# board_0_6v.net
KiCad netlist of a schematic drawn in EAGLE
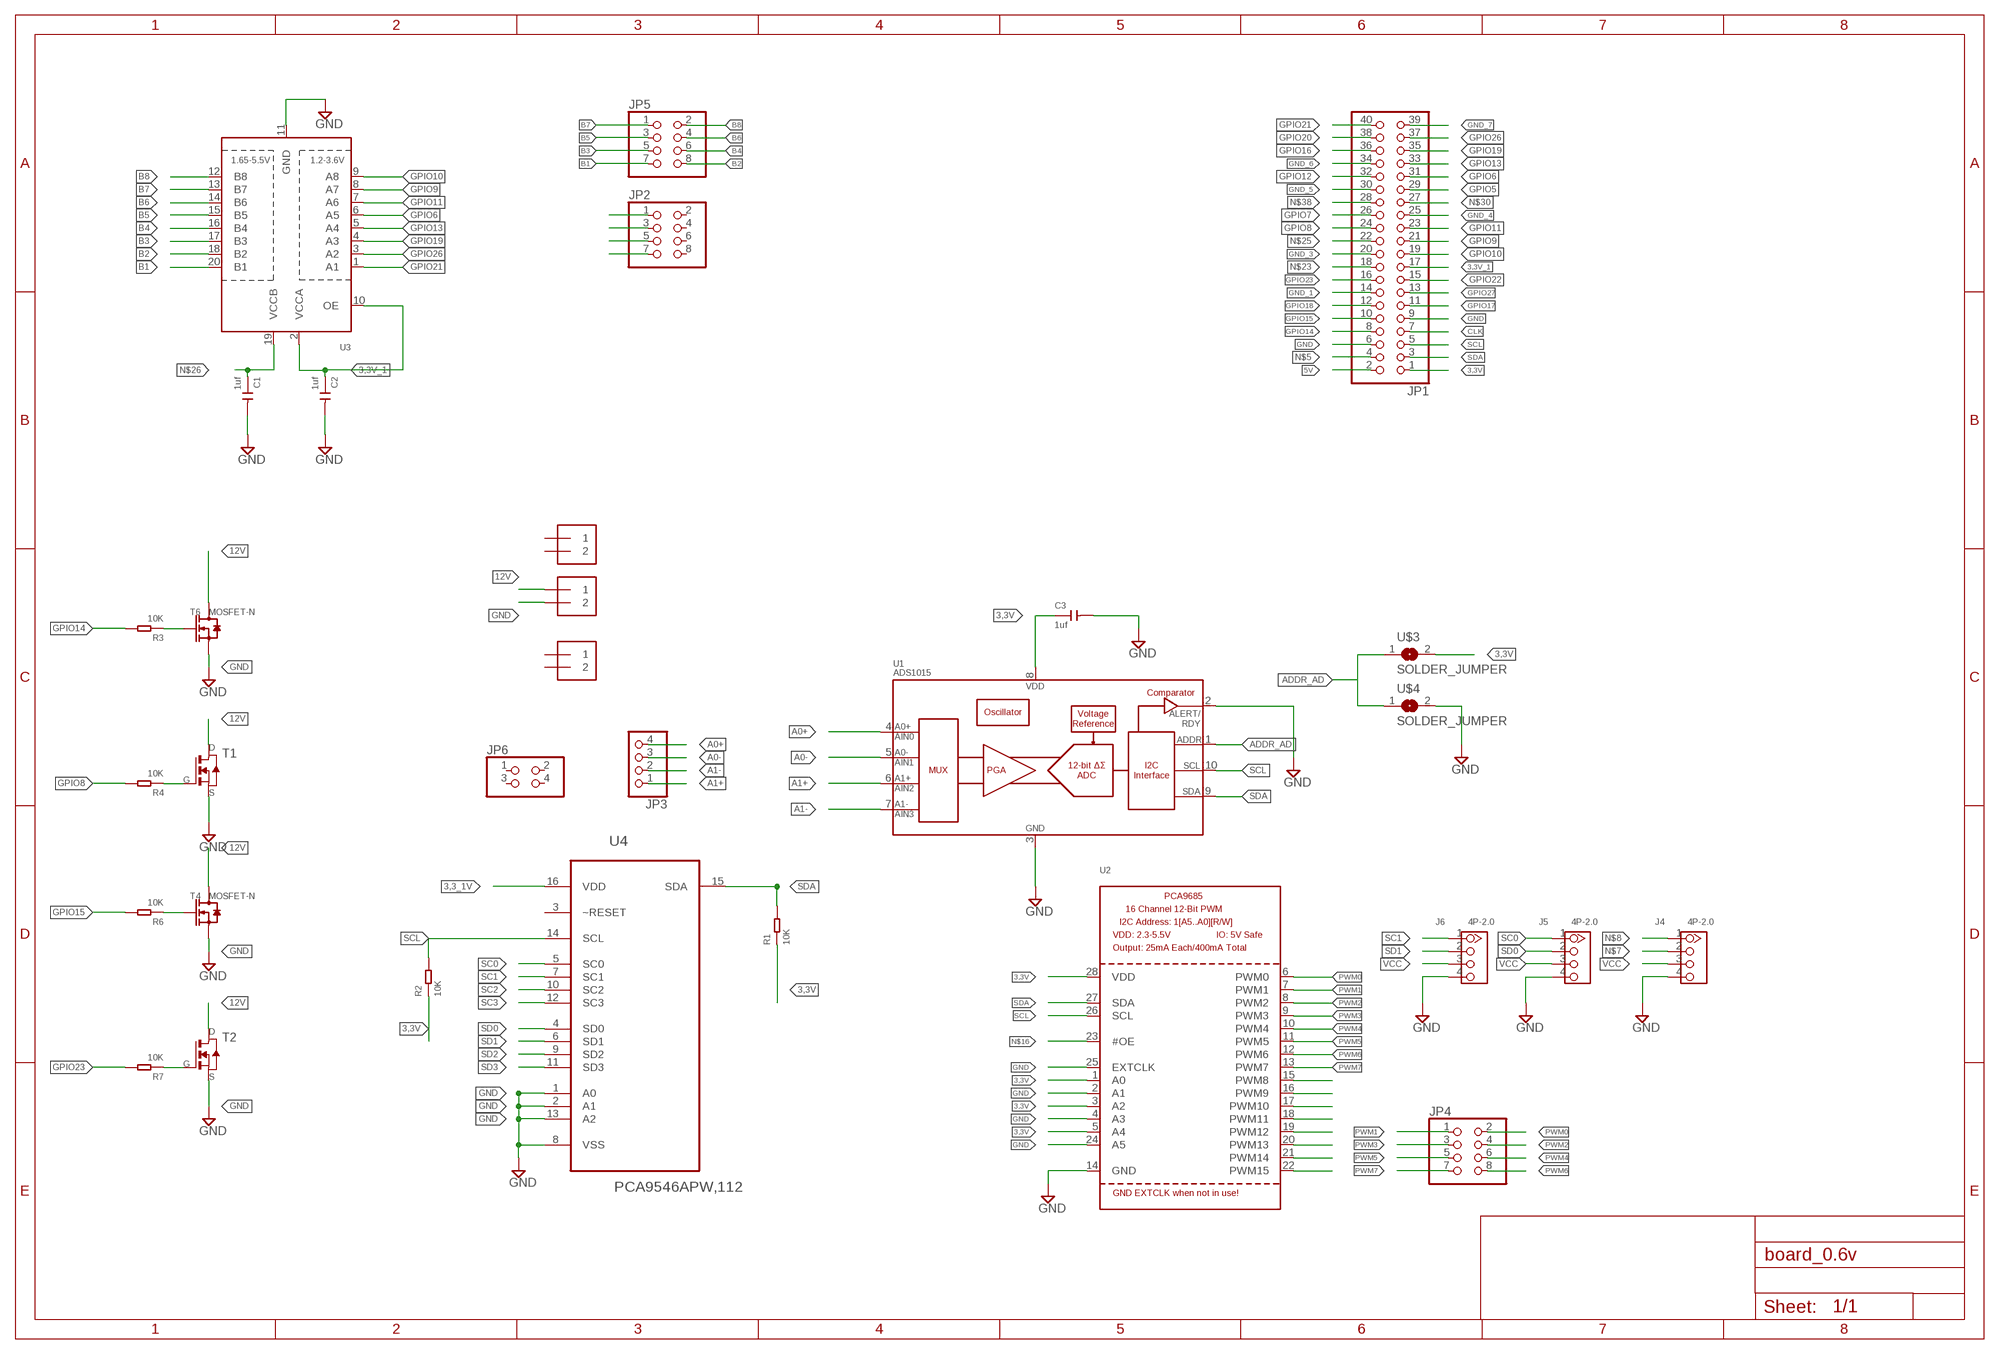
[diagram p0: schematic, sheet 1]

(export (version "E")
  (design (tool "Eeschema 10.0.6"))
  (components
    (comp (ref "C1")
      (value "1uf")
      (footprint "eagle-import:C0805")
      (fields (field (name "MPN") "CC0805KKX7R8BB105"))
      (libsource (lib "eagle-import") (part "CERAMIC-1UF-25V-10%-X7R(0805)"))
    )
    (comp (ref "C2")
      (value "1uf")
      (footprint "eagle-import:C0805")
      (fields (field (name "MPN") "CC0805KKX7R8BB105"))
      (libsource (lib "eagle-import") (part "CERAMIC-1UF-25V-10%-X7R(0805)"))
    )
    (comp (ref "C3")
      (value "1uf")
      (footprint "eagle-import:C0805")
      (fields (field (name "MPN") "CC0805KKX7R8BB105"))
      (libsource (lib "eagle-import") (part "CERAMIC-1UF-25V-10%-X7R(0805)"))
    )
    (comp (ref "J1")
      (value "1X2-3.5MM")
      (footprint "eagle-import:1X2-3.5MM")
      (libsource (lib "eagle-import") (part "1X2-3.5MM"))
    )
    (comp (ref "J2")
      (value "1X2-3.5MM")
      (footprint "eagle-import:1X2-3.5MM")
      (libsource (lib "eagle-import") (part "1X2-3.5MM"))
    )
    (comp (ref "J3")
      (value "1X2-3.5MM")
      (footprint "eagle-import:1X2-3.5MM")
      (libsource (lib "eagle-import") (part "1X2-3.5MM"))
    )
    (comp (ref "J4")
      (value "4P-2.0")
      (footprint "eagle-import:HW4-2.0")
      (libsource (lib "eagle-import") (part "GROVE-CONNECTOR-DIP(4P-2.0)"))
    )
    (comp (ref "J5")
      (value "4P-2.0")
      (footprint "eagle-import:HW4-2.0")
      (libsource (lib "eagle-import") (part "GROVE-CONNECTOR-DIP(4P-2.0)"))
    )
    (comp (ref "J6")
      (value "4P-2.0")
      (footprint "eagle-import:HW4-2.0")
      (libsource (lib "eagle-import") (part "GROVE-CONNECTOR-DIP(4P-2.0)"))
    )
    (comp (ref "JP1")
      (value "PINHD-2X20")
      (footprint "eagle-import:2X20")
      (libsource (lib "eagle-import") (part "PINHD-2X20"))
    )
    (comp (ref "JP2")
      (value "PINHD-2X4")
      (footprint "eagle-import:2X04")
      (libsource (lib "eagle-import") (part "PINHD-2X4"))
    )
    (comp (ref "JP3")
      (value "PINHD-1X4")
      (footprint "eagle-import:1X04")
      (libsource (lib "eagle-import") (part "PINHD-1X4"))
    )
    (comp (ref "JP4")
      (value "PINHD-2X4")
      (footprint "eagle-import:2X04")
      (libsource (lib "eagle-import") (part "PINHD-2X4"))
    )
    (comp (ref "JP5")
      (value "PINHD-2X4")
      (footprint "eagle-import:2X04")
      (libsource (lib "eagle-import") (part "PINHD-2X4"))
    )
    (comp (ref "JP6")
      (value "PINHD-2X2")
      (footprint "eagle-import:2X02")
      (libsource (lib "eagle-import") (part "PINHD-2X2"))
    )
    (comp (ref "R1")
      (value "10K")
      (footprint "eagle-import:R0805")
      (fields (field (name "MPN") "RC0805FR-0710KL"))
      (libsource (lib "eagle-import") (part "SMD-RES-10K-1%-1/8W(0805)"))
    )
    (comp (ref "R2")
      (value "10K")
      (footprint "eagle-import:R0805")
      (fields (field (name "MPN") "RC0805FR-0710KL"))
      (libsource (lib "eagle-import") (part "SMD-RES-10K-1%-1/8W(0805)"))
    )
    (comp (ref "R3")
      (value "10K")
      (footprint "eagle-import:R0805")
      (fields (field (name "MPN") "RC0805FR-0710KL"))
      (libsource (lib "eagle-import") (part "SMD-RES-10K-1%-1/8W(0805)"))
    )
    (comp (ref "R4")
      (value "10K")
      (footprint "eagle-import:R0805")
      (fields (field (name "MPN") "RC0805FR-0710KL"))
      (libsource (lib "eagle-import") (part "SMD-RES-10K-1%-1/8W(0805)"))
    )
    (comp (ref "R6")
      (value "10K")
      (footprint "eagle-import:R0805")
      (fields (field (name "MPN") "RC0805FR-0710KL"))
      (libsource (lib "eagle-import") (part "SMD-RES-10K-1%-1/8W(0805)"))
    )
    (comp (ref "R7")
      (value "10K")
      (footprint "eagle-import:R0805")
      (fields (field (name "MPN") "RC0805FR-0710KL"))
      (libsource (lib "eagle-import") (part "SMD-RES-10K-1%-1/8W(0805)"))
    )
    (comp (ref "T1")
      (value "NMOSFETTO252")
      (footprint "eagle-import:TO252")
      (libsource (lib "eagle-import") (part "NMOSFETTO252"))
    )
    (comp (ref "T2")
      (value "NMOSFETTO252")
      (footprint "eagle-import:TO252")
      (libsource (lib "eagle-import") (part "NMOSFETTO252"))
    )
    (comp (ref "T4")
      (value "MOSFET-N")
      (footprint "eagle-import:SOT-23")
      (libsource (lib "eagle-import") (part "MOSFET-N"))
    )
    (comp (ref "T6")
      (value "MOSFET-N")
      (footprint "eagle-import:SOT-23")
      (libsource (lib "eagle-import") (part "MOSFET-N"))
    )
    (comp (ref "U$3")
      (value "SOLDER_JUMPER")
      (footprint "eagle-import:SJFAB")
      (libsource (lib "eagle-import") (part "SOLDER_JUMPER"))
    )
    (comp (ref "U$4")
      (value "SOLDER_JUMPER")
      (footprint "eagle-import:SJFAB")
      (libsource (lib "eagle-import") (part "SOLDER_JUMPER"))
    )
    (comp (ref "U1")
      (value "ADS1015")
      (footprint "eagle-import:MSOP10")
      (libsource (lib "eagle-import") (part "ADS1015"))
    )
    (comp (ref "U2")
      (value "PCA9685")
      (footprint "eagle-import:TSSOP28")
      (libsource (lib "eagle-import") (part "PCA9685"))
    )
    (comp (ref "U3")
      (value "TXB0108PWR")
      (footprint "eagle-import:TSSOP20")
      (libsource (lib "eagle-import") (part "TXB0108PWR"))
    )
    (comp (ref "U4")
      (value "PCA9546APW,112")
      (footprint "eagle-import:SOP65P640X110-16N")
      (libsource (lib "eagle-import") (part "PCA9546APW,112"))
    )
  )
  (nets
    (net (code "1") (name "3,3V") (class "Default")
      (node (ref "C3") (pin "1") (pinfunction "1_1") (pintype "passive"))
      (node (ref "JP1") (pin "1") (pinfunction "1_1") (pintype "passive"))
      (node (ref "R1") (pin "1") (pinfunction "1_1") (pintype "passive"))
      (node (ref "R2") (pin "1") (pinfunction "1_1") (pintype "passive"))
      (node (ref "U$3") (pin "2") (pinfunction "2_2") (pintype "passive"))
      (node (ref "U1") (pin "8") (pinfunction "VDD_8") (pintype "bidirectional"))
      (node (ref "U2") (pin "1") (pinfunction "A0_1") (pintype "bidirectional"))
      (node (ref "U2") (pin "28") (pinfunction "VDD_28") (pintype "power_in"))
      (node (ref "U2") (pin "3") (pinfunction "A2_3") (pintype "bidirectional"))
      (node (ref "U2") (pin "5") (pinfunction "A4_5") (pintype "bidirectional"))
    )
    (net (code "2") (name "3,3V_1") (class "Default")
      (node (ref "C2") (pin "1") (pinfunction "1_1") (pintype "passive"))
      (node (ref "JP1") (pin "17") (pinfunction "17_17") (pintype "passive"))
      (node (ref "U3") (pin "10") (pinfunction "OE_10") (pintype "bidirectional"))
      (node (ref "U3") (pin "2") (pinfunction "VCCA_2") (pintype "bidirectional"))
    )
    (net (code "3") (name "3,3_1V") (class "Default")
      (node (ref "U4") (pin "16") (pinfunction "VDD_16") (pintype "power_in"))
    )
    (net (code "4") (name "5V") (class "Default")
      (node (ref "JP1") (pin "2") (pinfunction "2_2") (pintype "passive"))
    )
    (net (code "5") (name "12V") (class "Default")
      (node (ref "J2") (pin "1") (pinfunction "1_1") (pintype "passive"))
      (node (ref "T1") (pin "3") (pinfunction "D_3") (pintype "passive"))
      (node (ref "T2") (pin "3") (pinfunction "D_3") (pintype "passive"))
      (node (ref "T4") (pin "3") (pinfunction "D_3") (pintype "passive"))
      (node (ref "T6") (pin "3") (pinfunction "D_3") (pintype "passive"))
    )
    (net (code "6") (name "A0+") (class "Default")
      (node (ref "JP3") (pin "4") (pinfunction "4_4") (pintype "passive"))
      (node (ref "U1") (pin "4") (pinfunction "AIN0_4") (pintype "bidirectional"))
    )
    (net (code "7") (name "A0-") (class "Default")
      (node (ref "JP3") (pin "3") (pinfunction "3_3") (pintype "passive"))
      (node (ref "U1") (pin "5") (pinfunction "AIN1_5") (pintype "bidirectional"))
    )
    (net (code "8") (name "A1+") (class "Default")
      (node (ref "JP3") (pin "1") (pinfunction "1_1") (pintype "passive"))
      (node (ref "U1") (pin "6") (pinfunction "AIN2_6") (pintype "bidirectional"))
    )
    (net (code "9") (name "A1-") (class "Default")
      (node (ref "JP3") (pin "2") (pinfunction "2_2") (pintype "passive"))
      (node (ref "U1") (pin "7") (pinfunction "AIN3_7") (pintype "bidirectional"))
    )
    (net (code "10") (name "ADDR_AD") (class "Default")
      (node (ref "U$3") (pin "1") (pinfunction "1_1") (pintype "passive"))
      (node (ref "U$4") (pin "1") (pinfunction "1_1") (pintype "passive"))
      (node (ref "U1") (pin "1") (pinfunction "ADDR_1") (pintype "bidirectional"))
    )
    (net (code "11") (name "B1") (class "Default")
      (node (ref "JP5") (pin "7") (pinfunction "7_7") (pintype "passive"))
      (node (ref "U3") (pin "20") (pinfunction "B1_20") (pintype "bidirectional"))
    )
    (net (code "12") (name "B2") (class "Default")
      (node (ref "JP5") (pin "8") (pinfunction "8_8") (pintype "passive"))
      (node (ref "U3") (pin "18") (pinfunction "B2_18") (pintype "bidirectional"))
    )
    (net (code "13") (name "B3") (class "Default")
      (node (ref "JP5") (pin "5") (pinfunction "5_5") (pintype "passive"))
      (node (ref "U3") (pin "17") (pinfunction "B3_17") (pintype "bidirectional"))
    )
    (net (code "14") (name "B4") (class "Default")
      (node (ref "JP5") (pin "6") (pinfunction "6_6") (pintype "passive"))
      (node (ref "U3") (pin "16") (pinfunction "B4_16") (pintype "bidirectional"))
    )
    (net (code "15") (name "B5") (class "Default")
      (node (ref "JP5") (pin "3") (pinfunction "3_3") (pintype "passive"))
      (node (ref "U3") (pin "15") (pinfunction "B5_15") (pintype "bidirectional"))
    )
    (net (code "16") (name "B6") (class "Default")
      (node (ref "JP5") (pin "4") (pinfunction "4_4") (pintype "passive"))
      (node (ref "U3") (pin "14") (pinfunction "B6_14") (pintype "bidirectional"))
    )
    (net (code "17") (name "B7") (class "Default")
      (node (ref "JP5") (pin "1") (pinfunction "1_1") (pintype "passive"))
      (node (ref "U3") (pin "13") (pinfunction "B7_13") (pintype "bidirectional"))
    )
    (net (code "18") (name "B8") (class "Default")
      (node (ref "JP5") (pin "2") (pinfunction "2_2") (pintype "passive"))
      (node (ref "U3") (pin "12") (pinfunction "B8_12") (pintype "bidirectional"))
    )
    (net (code "19") (name "CLK") (class "Default")
      (node (ref "JP1") (pin "7") (pinfunction "7_7") (pintype "passive"))
    )
    (net (code "20") (name "GND") (class "Default")
      (node (ref "C1") (pin "2") (pinfunction "2_2") (pintype "passive"))
      (node (ref "C2") (pin "2") (pinfunction "2_2") (pintype "passive"))
      (node (ref "C3") (pin "2") (pinfunction "2_2") (pintype "passive"))
      (node (ref "J2") (pin "2") (pinfunction "2_2") (pintype "passive"))
      (node (ref "J4") (pin "4") (pinfunction "4_4") (pintype "bidirectional"))
      (node (ref "J5") (pin "4") (pinfunction "4_4") (pintype "bidirectional"))
      (node (ref "J6") (pin "4") (pinfunction "4_4") (pintype "bidirectional"))
      (node (ref "JP1") (pin "6") (pinfunction "6_6") (pintype "passive"))
      (node (ref "JP1") (pin "9") (pinfunction "9_9") (pintype "passive"))
      (node (ref "T1") (pin "2") (pinfunction "S_2") (pintype "passive"))
      (node (ref "T2") (pin "2") (pinfunction "S_2") (pintype "passive"))
      (node (ref "T4") (pin "2") (pinfunction "S_2") (pintype "passive"))
      (node (ref "T6") (pin "2") (pinfunction "S_2") (pintype "passive"))
      (node (ref "U$4") (pin "2") (pinfunction "2_2") (pintype "passive"))
      (node (ref "U1") (pin "2") (pinfunction "ALERT/RDY_2") (pintype "bidirectional"))
      (node (ref "U1") (pin "3") (pinfunction "VSS_3") (pintype "bidirectional"))
      (node (ref "U2") (pin "14") (pinfunction "GND_14") (pintype "power_in"))
      (node (ref "U2") (pin "2") (pinfunction "A1_2") (pintype "bidirectional"))
      (node (ref "U2") (pin "24") (pinfunction "A5_24") (pintype "bidirectional"))
      (node (ref "U2") (pin "25") (pinfunction "EXTCLK_25") (pintype "input"))
      (node (ref "U2") (pin "4") (pinfunction "A3_4") (pintype "bidirectional"))
      (node (ref "U3") (pin "11") (pinfunction "GND_11") (pintype "bidirectional"))
      (node (ref "U4") (pin "1") (pinfunction "A0_1") (pintype "input"))
      (node (ref "U4") (pin "13") (pinfunction "A2_13") (pintype "input"))
      (node (ref "U4") (pin "2") (pinfunction "A1_2") (pintype "input"))
      (node (ref "U4") (pin "8") (pinfunction "VSS_8") (pintype "passive"))
    )
    (net (code "21") (name "GND_1") (class "Default")
      (node (ref "JP1") (pin "14") (pinfunction "14_14") (pintype "passive"))
    )
    (net (code "22") (name "GND_3") (class "Default")
      (node (ref "JP1") (pin "20") (pinfunction "20_20") (pintype "passive"))
    )
    (net (code "23") (name "GND_4") (class "Default")
      (node (ref "JP1") (pin "25") (pinfunction "25_25") (pintype "passive"))
    )
    (net (code "24") (name "GND_5") (class "Default")
      (node (ref "JP1") (pin "30") (pinfunction "30_30") (pintype "passive"))
    )
    (net (code "25") (name "GND_6") (class "Default")
      (node (ref "JP1") (pin "34") (pinfunction "34_34") (pintype "passive"))
    )
    (net (code "26") (name "GND_7") (class "Default")
      (node (ref "JP1") (pin "39") (pinfunction "39_39") (pintype "passive"))
    )
    (net (code "27") (name "GPIO5") (class "Default")
      (node (ref "JP1") (pin "29") (pinfunction "29_29") (pintype "passive"))
    )
    (net (code "28") (name "GPIO6") (class "Default")
      (node (ref "JP1") (pin "31") (pinfunction "31_31") (pintype "passive"))
      (node (ref "U3") (pin "6") (pinfunction "A5_6") (pintype "bidirectional"))
    )
    (net (code "29") (name "GPIO7") (class "Default")
      (node (ref "JP1") (pin "26") (pinfunction "26_26") (pintype "passive"))
    )
    (net (code "30") (name "GPIO8") (class "Default")
      (node (ref "JP1") (pin "24") (pinfunction "24_24") (pintype "passive"))
      (node (ref "R4") (pin "2") (pinfunction "2_2") (pintype "passive"))
    )
    (net (code "31") (name "GPIO9") (class "Default")
      (node (ref "JP1") (pin "21") (pinfunction "21_21") (pintype "passive"))
      (node (ref "U3") (pin "8") (pinfunction "A7_8") (pintype "bidirectional"))
    )
    (net (code "32") (name "GPIO10") (class "Default")
      (node (ref "JP1") (pin "19") (pinfunction "19_19") (pintype "passive"))
      (node (ref "U3") (pin "9") (pinfunction "A8_9") (pintype "bidirectional"))
    )
    (net (code "33") (name "GPIO11") (class "Default")
      (node (ref "JP1") (pin "23") (pinfunction "23_23") (pintype "passive"))
      (node (ref "U3") (pin "7") (pinfunction "A6_7") (pintype "bidirectional"))
    )
    (net (code "34") (name "GPIO12") (class "Default")
      (node (ref "JP1") (pin "32") (pinfunction "32_32") (pintype "passive"))
    )
    (net (code "35") (name "GPIO13") (class "Default")
      (node (ref "JP1") (pin "33") (pinfunction "33_33") (pintype "passive"))
      (node (ref "U3") (pin "5") (pinfunction "A4_5") (pintype "bidirectional"))
    )
    (net (code "36") (name "GPIO14") (class "Default")
      (node (ref "JP1") (pin "8") (pinfunction "8_8") (pintype "passive"))
      (node (ref "R3") (pin "2") (pinfunction "2_2") (pintype "passive"))
    )
    (net (code "37") (name "GPIO15") (class "Default")
      (node (ref "JP1") (pin "10") (pinfunction "10_10") (pintype "passive"))
      (node (ref "R6") (pin "2") (pinfunction "2_2") (pintype "passive"))
    )
    (net (code "38") (name "GPIO16") (class "Default")
      (node (ref "JP1") (pin "36") (pinfunction "36_36") (pintype "passive"))
    )
    (net (code "39") (name "GPIO17") (class "Default")
      (node (ref "JP1") (pin "11") (pinfunction "11_11") (pintype "passive"))
    )
    (net (code "40") (name "GPIO18") (class "Default")
      (node (ref "JP1") (pin "12") (pinfunction "12_12") (pintype "passive"))
    )
    (net (code "41") (name "GPIO19") (class "Default")
      (node (ref "JP1") (pin "35") (pinfunction "35_35") (pintype "passive"))
      (node (ref "U3") (pin "4") (pinfunction "A3_4") (pintype "bidirectional"))
    )
    (net (code "42") (name "GPIO20") (class "Default")
      (node (ref "JP1") (pin "38") (pinfunction "38_38") (pintype "passive"))
    )
    (net (code "43") (name "GPIO21") (class "Default")
      (node (ref "JP1") (pin "40") (pinfunction "40_40") (pintype "passive"))
      (node (ref "U3") (pin "1") (pinfunction "A1_1") (pintype "bidirectional"))
    )
    (net (code "44") (name "GPIO22") (class "Default")
      (node (ref "JP1") (pin "15") (pinfunction "15_15") (pintype "passive"))
    )
    (net (code "45") (name "GPIO23") (class "Default")
      (node (ref "JP1") (pin "16") (pinfunction "16_16") (pintype "passive"))
      (node (ref "R7") (pin "2") (pinfunction "2_2") (pintype "passive"))
    )
    (net (code "46") (name "GPIO26") (class "Default")
      (node (ref "JP1") (pin "37") (pinfunction "37_37") (pintype "passive"))
      (node (ref "U3") (pin "3") (pinfunction "A2_3") (pintype "bidirectional"))
    )
    (net (code "47") (name "GPIO27") (class "Default")
      (node (ref "JP1") (pin "13") (pinfunction "13_13") (pintype "passive"))
    )
    (net (code "48") (name "N$5") (class "Default")
      (node (ref "JP1") (pin "4") (pinfunction "4_4") (pintype "passive"))
    )
    (net (code "49") (name "N$7") (class "Default")
      (node (ref "J4") (pin "2") (pinfunction "2_2") (pintype "bidirectional"))
    )
    (net (code "50") (name "N$8") (class "Default")
      (node (ref "J4") (pin "1") (pinfunction "1_1") (pintype "bidirectional"))
    )
    (net (code "51") (name "N$16") (class "Default")
      (node (ref "U2") (pin "23") (pinfunction "#OE_23") (pintype "input"))
    )
    (net (code "52") (name "N$23") (class "Default")
      (node (ref "JP1") (pin "18") (pinfunction "18_18") (pintype "passive"))
    )
    (net (code "53") (name "N$25") (class "Default")
      (node (ref "JP1") (pin "22") (pinfunction "22_22") (pintype "passive"))
    )
    (net (code "54") (name "N$26") (class "Default")
      (node (ref "C1") (pin "1") (pinfunction "1_1") (pintype "passive"))
      (node (ref "U3") (pin "19") (pinfunction "VCCB_19") (pintype "bidirectional"))
    )
    (net (code "55") (name "N$30") (class "Default")
      (node (ref "JP1") (pin "27") (pinfunction "27_27") (pintype "passive"))
    )
    (net (code "56") (name "N$38") (class "Default")
      (node (ref "JP1") (pin "28") (pinfunction "28_28") (pintype "passive"))
    )
    (net (code "57") (name "Net-(T1-G)") (class "Default")
      (node (ref "R4") (pin "1") (pinfunction "1_1") (pintype "passive"))
      (node (ref "T1") (pin "1") (pinfunction "G_1") (pintype "passive"))
    )
    (net (code "58") (name "Net-(T2-G)") (class "Default")
      (node (ref "R7") (pin "1") (pinfunction "1_1") (pintype "passive"))
      (node (ref "T2") (pin "1") (pinfunction "G_1") (pintype "passive"))
    )
    (net (code "59") (name "Net-(T4-G)") (class "Default")
      (node (ref "R6") (pin "1") (pinfunction "1_1") (pintype "passive"))
      (node (ref "T4") (pin "1") (pinfunction "G_1") (pintype "passive"))
    )
    (net (code "60") (name "Net-(T6-G)") (class "Default")
      (node (ref "R3") (pin "1") (pinfunction "1_1") (pintype "passive"))
      (node (ref "T6") (pin "1") (pinfunction "G_1") (pintype "passive"))
    )
    (net (code "61") (name "PWM0") (class "Default")
      (node (ref "JP4") (pin "2") (pinfunction "2_2") (pintype "passive"))
      (node (ref "U2") (pin "6") (pinfunction "PWM0_6") (pintype "output"))
    )
    (net (code "62") (name "PWM1") (class "Default")
      (node (ref "JP4") (pin "1") (pinfunction "1_1") (pintype "passive"))
      (node (ref "U2") (pin "7") (pinfunction "PWM1_7") (pintype "output"))
    )
    (net (code "63") (name "PWM2") (class "Default")
      (node (ref "JP4") (pin "4") (pinfunction "4_4") (pintype "passive"))
      (node (ref "U2") (pin "8") (pinfunction "PWM2_8") (pintype "output"))
    )
    (net (code "64") (name "PWM3") (class "Default")
      (node (ref "JP4") (pin "3") (pinfunction "3_3") (pintype "passive"))
      (node (ref "U2") (pin "9") (pinfunction "PWM3_9") (pintype "output"))
    )
    (net (code "65") (name "PWM4") (class "Default")
      (node (ref "JP4") (pin "6") (pinfunction "6_6") (pintype "passive"))
      (node (ref "U2") (pin "10") (pinfunction "PWM4_10") (pintype "output"))
    )
    (net (code "66") (name "PWM5") (class "Default")
      (node (ref "JP4") (pin "5") (pinfunction "5_5") (pintype "passive"))
      (node (ref "U2") (pin "11") (pinfunction "PWM5_11") (pintype "output"))
    )
    (net (code "67") (name "PWM6") (class "Default")
      (node (ref "JP4") (pin "8") (pinfunction "8_8") (pintype "passive"))
      (node (ref "U2") (pin "12") (pinfunction "PWM6_12") (pintype "output"))
    )
    (net (code "68") (name "PWM7") (class "Default")
      (node (ref "JP4") (pin "7") (pinfunction "7_7") (pintype "passive"))
      (node (ref "U2") (pin "13") (pinfunction "PWM7_13") (pintype "output"))
    )
    (net (code "69") (name "SC0") (class "Default")
      (node (ref "J5") (pin "1") (pinfunction "1_1") (pintype "bidirectional"))
      (node (ref "U4") (pin "5") (pinfunction "SC0_5") (pintype "input"))
    )
    (net (code "70") (name "SC1") (class "Default")
      (node (ref "J6") (pin "1") (pinfunction "1_1") (pintype "bidirectional"))
      (node (ref "U4") (pin "7") (pinfunction "SC1_7") (pintype "input"))
    )
    (net (code "71") (name "SC2") (class "Default")
      (node (ref "U4") (pin "10") (pinfunction "SC2_10") (pintype "input"))
    )
    (net (code "72") (name "SC3") (class "Default")
      (node (ref "U4") (pin "12") (pinfunction "SC3_12") (pintype "input"))
    )
    (net (code "73") (name "SCL") (class "Default")
      (node (ref "JP1") (pin "5") (pinfunction "5_5") (pintype "passive"))
      (node (ref "R2") (pin "2") (pinfunction "2_2") (pintype "passive"))
      (node (ref "U1") (pin "10") (pinfunction "SCL_10") (pintype "bidirectional"))
      (node (ref "U2") (pin "26") (pinfunction "SCL_26") (pintype "bidirectional"))
      (node (ref "U4") (pin "14") (pinfunction "SCL_14") (pintype "bidirectional"))
    )
    (net (code "74") (name "SD0") (class "Default")
      (node (ref "J5") (pin "2") (pinfunction "2_2") (pintype "bidirectional"))
      (node (ref "U4") (pin "4") (pinfunction "SD0_4") (pintype "input"))
    )
    (net (code "75") (name "SD1") (class "Default")
      (node (ref "J6") (pin "2") (pinfunction "2_2") (pintype "bidirectional"))
      (node (ref "U4") (pin "6") (pinfunction "SD1_6") (pintype "input"))
    )
    (net (code "76") (name "SD2") (class "Default")
      (node (ref "U4") (pin "9") (pinfunction "SD2_9") (pintype "input"))
    )
    (net (code "77") (name "SD3") (class "Default")
      (node (ref "U4") (pin "11") (pinfunction "SD3_11") (pintype "input"))
    )
    (net (code "78") (name "SDA") (class "Default")
      (node (ref "JP1") (pin "3") (pinfunction "3_3") (pintype "passive"))
      (node (ref "R1") (pin "2") (pinfunction "2_2") (pintype "passive"))
      (node (ref "U1") (pin "9") (pinfunction "SDA_9") (pintype "bidirectional"))
      (node (ref "U2") (pin "27") (pinfunction "SDA_27") (pintype "bidirectional"))
      (node (ref "U4") (pin "15") (pinfunction "SDA_15") (pintype "bidirectional"))
    )
    (net (code "79") (name "VCC") (class "Default")
      (node (ref "J4") (pin "3") (pinfunction "3_3") (pintype "bidirectional"))
      (node (ref "J5") (pin "3") (pinfunction "3_3") (pintype "bidirectional"))
      (node (ref "J6") (pin "3") (pinfunction "3_3") (pintype "bidirectional"))
    )
    (net (code "80") (name "unconnected-(J1-Pad1)") (class "Default")
      (node (ref "J1") (pin "1") (pinfunction "1_1") (pintype "passive"))
    )
    (net (code "81") (name "unconnected-(J1-Pad2)") (class "Default")
      (node (ref "J1") (pin "2") (pinfunction "2_2") (pintype "passive"))
    )
    (net (code "82") (name "unconnected-(J3-Pad1)") (class "Default")
      (node (ref "J3") (pin "1") (pinfunction "1_1") (pintype "passive"))
    )
    (net (code "83") (name "unconnected-(J3-Pad2)") (class "Default")
      (node (ref "J3") (pin "2") (pinfunction "2_2") (pintype "passive"))
    )
    (net (code "84") (name "unconnected-(JP2-Pad1)") (class "Default")
      (node (ref "JP2") (pin "1") (pinfunction "1_1") (pintype "passive"))
    )
    (net (code "85") (name "unconnected-(JP2-Pad2)") (class "Default")
      (node (ref "JP2") (pin "2") (pinfunction "2_2") (pintype "passive"))
    )
    (net (code "86") (name "unconnected-(JP2-Pad3)") (class "Default")
      (node (ref "JP2") (pin "3") (pinfunction "3_3") (pintype "passive"))
    )
    (net (code "87") (name "unconnected-(JP2-Pad4)") (class "Default")
      (node (ref "JP2") (pin "4") (pinfunction "4_4") (pintype "passive"))
    )
    (net (code "88") (name "unconnected-(JP2-Pad5)") (class "Default")
      (node (ref "JP2") (pin "5") (pinfunction "5_5") (pintype "passive"))
    )
    (net (code "89") (name "unconnected-(JP2-Pad6)") (class "Default")
      (node (ref "JP2") (pin "6") (pinfunction "6_6") (pintype "passive"))
    )
    (net (code "90") (name "unconnected-(JP2-Pad7)") (class "Default")
      (node (ref "JP2") (pin "7") (pinfunction "7_7") (pintype "passive"))
    )
    (net (code "91") (name "unconnected-(JP2-Pad8)") (class "Default")
      (node (ref "JP2") (pin "8") (pinfunction "8_8") (pintype "passive"))
    )
    (net (code "92") (name "unconnected-(JP6-Pad1)") (class "Default")
      (node (ref "JP6") (pin "1") (pinfunction "1_1") (pintype "passive"))
    )
    (net (code "93") (name "unconnected-(JP6-Pad2)") (class "Default")
      (node (ref "JP6") (pin "2") (pinfunction "2_2") (pintype "passive"))
    )
    (net (code "94") (name "unconnected-(JP6-Pad3)") (class "Default")
      (node (ref "JP6") (pin "3") (pinfunction "3_3") (pintype "passive"))
    )
    (net (code "95") (name "unconnected-(JP6-Pad4)") (class "Default")
      (node (ref "JP6") (pin "4") (pinfunction "4_4") (pintype "passive"))
    )
    (net (code "96") (name "unconnected-(U2-PWM8-Pad15)") (class "Default")
      (node (ref "U2") (pin "15") (pinfunction "PWM8_15") (pintype "output"))
    )
    (net (code "97") (name "unconnected-(U2-PWM9-Pad16)") (class "Default")
      (node (ref "U2") (pin "16") (pinfunction "PWM9_16") (pintype "output"))
    )
    (net (code "98") (name "unconnected-(U2-PWM10-Pad17)") (class "Default")
      (node (ref "U2") (pin "17") (pinfunction "PWM10_17") (pintype "output"))
    )
    (net (code "99") (name "unconnected-(U2-PWM11-Pad18)") (class "Default")
      (node (ref "U2") (pin "18") (pinfunction "PWM11_18") (pintype "output"))
    )
    (net (code "100") (name "unconnected-(U2-PWM12-Pad19)") (class "Default")
      (node (ref "U2") (pin "19") (pinfunction "PWM12_19") (pintype "output"))
    )
    (net (code "101") (name "unconnected-(U2-PWM13-Pad20)") (class "Default")
      (node (ref "U2") (pin "20") (pinfunction "PWM13_20") (pintype "output"))
    )
    (net (code "102") (name "unconnected-(U2-PWM14-Pad21)") (class "Default")
      (node (ref "U2") (pin "21") (pinfunction "PWM14_21") (pintype "output"))
    )
    (net (code "103") (name "unconnected-(U2-PWM15-Pad22)") (class "Default")
      (node (ref "U2") (pin "22") (pinfunction "PWM15_22") (pintype "output"))
    )
    (net (code "104") (name "unconnected-(U4-~{RESET}-Pad3)") (class "Default")
      (node (ref "U4") (pin "3") (pinfunction "~{RESET}_3") (pintype "input"))
    )
  )
)
